# Sheet1.net
KiCad netlist of a schematic drawn in Altium Designer
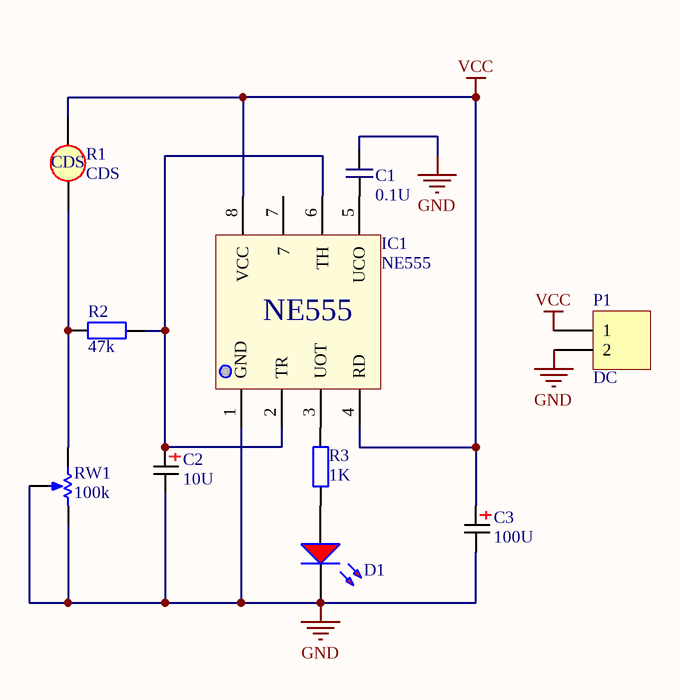
[diagram p0: Sheet1.SchDoc]

(export (version "E")
  (design (tool "Eeschema 10.0.6"))
  (components
    (comp (ref "C1") (value "0.1U") (footprint "RAD0.1") (libsource (lib "MY") (part "Cap")))
    (comp (ref "C2") (value "10U") (footprint "CF0.1") (libsource (lib "MY") (part "Cap Pol")))
    (comp (ref "C3") (value "100U") (footprint "CF0.1") (libsource (lib "MY") (part "Cap Pol")))
    (comp (ref "D1")
      (value "LED0")
      (footprint "LED")
      (fields (field (name "PUBLISHER") "Altium Limited"))
      (libsource (lib "MY") (part "LED0"))
    )
    (comp (ref "IC1") (value "NE555") (footprint "DIP-8") (libsource (lib "MY") (part "NE555")))
    (comp (ref "P1")
      (value "DC")
      (footprint "HDR1X2")
      (description "Header, 2-Pin")
      (fields (field (name "PUBLISHER") "Altium Limited"))
      (libsource (lib "Miscellaneous Connectors") (part "Header 2"))
    )
    (comp (ref "R1") (value "CDS") (footprint "CDS") (libsource (lib "MY") (part "CDS")))
    (comp (ref "R2")
      (value "47k")
      (footprint "AXIAL-0.3")
      (description "Resistor")
      (fields (field (name "PUBLISHER") "Altium Limited"))
      (libsource (lib "") (part "Res_1"))
    )
    (comp (ref "R3")
      (value "1K")
      (footprint "AXIAL-0.3")
      (description "Resistor")
      (fields (field (name "PUBLISHER") "Altium Limited"))
      (libsource (lib "MY") (part "Res"))
    )
    (comp (ref "RW1") (value "100k") (footprint "RW1") (libsource (lib "MY") (part "RW1")))
  )
  (nets
    (net (code "1") (name "GND") (class "Default")
      (node (ref "C1") (pin "2") (pinfunction "2_2") (pintype "passive"))
      (node (ref "C2") (pin "2") (pinfunction "2_2") (pintype "passive"))
      (node (ref "C3") (pin "2") (pinfunction "2_2") (pintype "passive"))
      (node (ref "D1") (pin "2") (pinfunction "K_2") (pintype "passive"))
      (node (ref "IC1") (pin "1") (pinfunction "GND_1") (pintype "passive"))
      (node (ref "P1") (pin "2") (pinfunction "2_2") (pintype "passive"))
      (node (ref "RW1") (pin "2") (pinfunction "TAP_2") (pintype "passive"))
      (node (ref "RW1") (pin "3") (pinfunction "BOT_3") (pintype "passive"))
    )
    (net (code "2") (name "Net-(D1-A)") (class "Default")
      (node (ref "D1") (pin "1") (pinfunction "A_1") (pintype "passive"))
      (node (ref "R3") (pin "1") (pinfunction "1_1") (pintype "passive"))
    )
    (net (code "3") (name "Net-(IC1-TH)") (class "Default")
      (node (ref "C2") (pin "1") (pinfunction "1_1") (pintype "passive"))
      (node (ref "IC1") (pin "2") (pinfunction "TR_2") (pintype "passive"))
      (node (ref "IC1") (pin "6") (pinfunction "TH_6") (pintype "passive"))
      (node (ref "R2") (pin "2") (pinfunction "2_2") (pintype "passive"))
    )
    (net (code "4") (name "Net-(IC1-UCO)") (class "Default")
      (node (ref "C1") (pin "1") (pinfunction "1_1") (pintype "passive"))
      (node (ref "IC1") (pin "5") (pinfunction "UCO_5") (pintype "passive"))
    )
    (net (code "5") (name "Net-(IC1-UOT)") (class "Default")
      (node (ref "IC1") (pin "3") (pinfunction "UOT_3") (pintype "passive"))
      (node (ref "R3") (pin "2") (pinfunction "2_2") (pintype "passive"))
    )
    (net (code "6") (name "Net-(RW1-TOP)") (class "Default")
      (node (ref "R1") (pin "2") (pintype "passive"))
      (node (ref "R2") (pin "1") (pinfunction "1_1") (pintype "passive"))
      (node (ref "RW1") (pin "1") (pinfunction "TOP_1") (pintype "passive"))
    )
    (net (code "7") (name "VCC") (class "Default")
      (node (ref "C3") (pin "1") (pinfunction "1_1") (pintype "passive"))
      (node (ref "IC1") (pin "4") (pinfunction "RD_4") (pintype "passive"))
      (node (ref "IC1") (pin "8") (pinfunction "VCC_8") (pintype "passive"))
      (node (ref "P1") (pin "1") (pinfunction "1_1") (pintype "passive"))
      (node (ref "R1") (pin "1") (pintype "passive"))
    )
    (net (code "8") (name "unconnected-(IC1-Pad7)") (class "Default")
      (node (ref "IC1") (pin "7") (pinfunction "7_7") (pintype "passive"))
    )
  )
)
